# v1.net
KiCad netlist of a schematic drawn in EAGLE
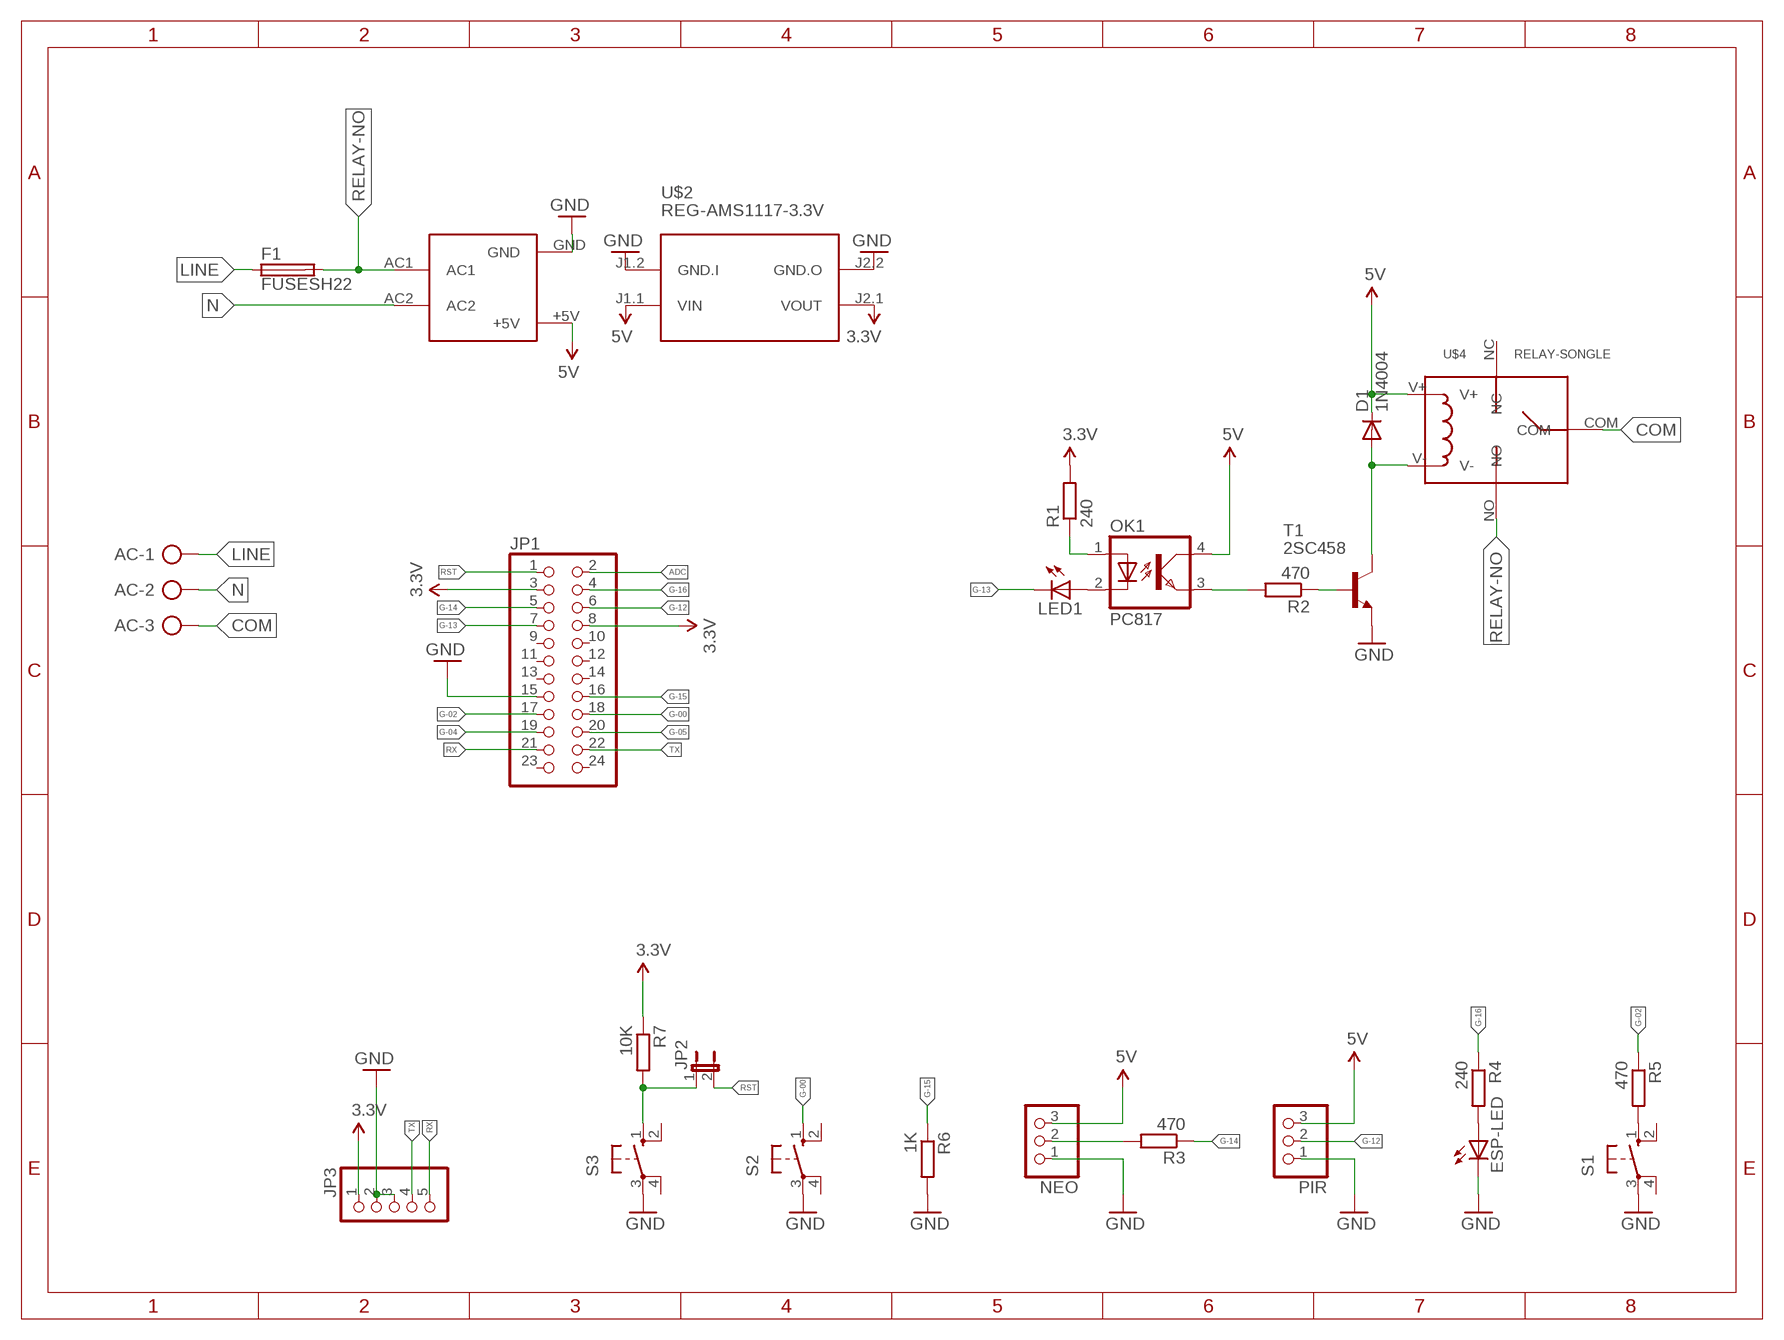
[diagram p0: schematic, sheet 1]

(export (version "E")
  (design (tool "Eeschema 10.0.6"))
  (components
    (comp (ref "AC")
      (value "AK300/3")
      (footprint "eagle-import:AK300_3")
      (libsource (lib "eagle-import") (part "AK300/3"))
    )
    (comp (ref "D1")
      (value "1N4004")
      (footprint "eagle-import:DO41-10")
      (libsource (lib "eagle-import") (part "1N4004"))
    )
    (comp (ref "ESP-LED")
      (value "LED5MM")
      (footprint "eagle-import:LED5MM")
      (libsource (lib "eagle-import") (part "LED5MM"))
    )
    (comp (ref "F1")
      (value "FUSESH22")
      (footprint "eagle-import:SH22")
      (libsource (lib "eagle-import") (part "FUSESH22"))
    )
    (comp (ref "JP1")
      (value "PINHD-2X12")
      (footprint "eagle-import:2X12")
      (libsource (lib "eagle-import") (part "PINHD-2X12"))
    )
    (comp (ref "JP2")
      (value "JUMPER-2PTH")
      (footprint "eagle-import:1X02")
      (libsource (lib "eagle-import") (part "JUMPER-2PTH"))
    )
    (comp (ref "JP3")
      (value "PINHD-1X5")
      (footprint "eagle-import:1X05")
      (libsource (lib "eagle-import") (part "PINHD-1X5"))
    )
    (comp (ref "LED1")
      (value "LED5MM")
      (footprint "eagle-import:LED5MM")
      (libsource (lib "eagle-import") (part "LED5MM"))
    )
    (comp (ref "NEO")
      (value "PINHD-1X3")
      (footprint "eagle-import:1X03")
      (libsource (lib "eagle-import") (part "PINHD-1X3"))
    )
    (comp (ref "OK1")
      (value "PC817")
      (footprint "eagle-import:DIL04")
      (fields (field (name "MPN") "PC817X4J000F"))
      (libsource (lib "eagle-import") (part "PC817"))
    )
    (comp (ref "PIR")
      (value "PINHD-1X3")
      (footprint "eagle-import:1X03")
      (libsource (lib "eagle-import") (part "PINHD-1X3"))
    )
    (comp (ref "R1")
      (value "240")
      (footprint "eagle-import:0204_5")
      (libsource (lib "eagle-import") (part "R-EU_0204/5"))
    )
    (comp (ref "R2")
      (value "470")
      (footprint "eagle-import:0204_5")
      (libsource (lib "eagle-import") (part "R-EU_0204/5"))
    )
    (comp (ref "R3")
      (value "470")
      (footprint "eagle-import:0204_5")
      (libsource (lib "eagle-import") (part "R-EU_0204/5"))
    )
    (comp (ref "R4")
      (value "240")
      (footprint "eagle-import:0204_5")
      (libsource (lib "eagle-import") (part "R-EU_0204/5"))
    )
    (comp (ref "R5")
      (value "470")
      (footprint "eagle-import:0204_5")
      (libsource (lib "eagle-import") (part "R-EU_0204/5"))
    )
    (comp (ref "R6")
      (value "1K")
      (footprint "eagle-import:0204_5")
      (libsource (lib "eagle-import") (part "R-EU_0204/5"))
    )
    (comp (ref "R7")
      (value "10K")
      (footprint "eagle-import:0204_5")
      (libsource (lib "eagle-import") (part "R-EU_0204/5"))
    )
    (comp (ref "S1")
      (value "10-XX")
      (footprint "eagle-import:B3F-10XX")
      (fields (field (name "MPN") "B3F-1000"))
      (libsource (lib "eagle-import") (part "10-XX"))
    )
    (comp (ref "S2")
      (value "10-XX")
      (footprint "eagle-import:B3F-10XX")
      (fields (field (name "MPN") "B3F-1000"))
      (libsource (lib "eagle-import") (part "10-XX"))
    )
    (comp (ref "S3")
      (value "10-XX")
      (footprint "eagle-import:B3F-10XX")
      (fields (field (name "MPN") "B3F-1000"))
      (libsource (lib "eagle-import") (part "10-XX"))
    )
    (comp (ref "T1")
      (value "2SC458")
      (footprint "eagle-import:TO92-ECB")
      (libsource (lib "eagle-import") (part "2SC458"))
    )
    (comp (ref "U$1")
      (value "HLK-PM01")
      (footprint "eagle-import:HLK-PM01")
      (libsource (lib "eagle-import") (part "HLK-PM01"))
    )
    (comp (ref "U$2")
      (value "REG-AMS1117-3.3V")
      (footprint "eagle-import:REG-AMS1117")
      (libsource (lib "eagle-import") (part "REG-AMS1117-3.3V"))
    )
    (comp (ref "U$4")
      (value "RELAY-SONGLE")
      (footprint "eagle-import:RELAY-SONGLE")
      (libsource (lib "eagle-import") (part "RELAY-SONGLE"))
    )
  )
  (nets
    (net (code "1") (name "3.3V") (class "Default")
      (node (ref "JP1") (pin "3") (pinfunction "3_3") (pintype "passive"))
      (node (ref "JP1") (pin "8") (pinfunction "8_8") (pintype "passive"))
      (node (ref "JP3") (pin "1") (pinfunction "1_1") (pintype "passive"))
      (node (ref "R1") (pin "2") (pinfunction "2_2") (pintype "passive"))
      (node (ref "R7") (pin "1") (pinfunction "1_1") (pintype "passive"))
      (node (ref "U$2") (pin "J2.1") (pinfunction "VOUT_J2.1") (pintype "bidirectional"))
    )
    (net (code "2") (name "5V") (class "Default")
      (node (ref "D1") (pin "C") (pinfunction "C_C") (pintype "passive"))
      (node (ref "NEO") (pin "3") (pinfunction "3_3") (pintype "passive"))
      (node (ref "OK1") (pin "4") (pinfunction "COL_4") (pintype "passive"))
      (node (ref "PIR") (pin "3") (pinfunction "3_3") (pintype "passive"))
      (node (ref "U$1") (pin "+5V") (pinfunction "+5V_+5V") (pintype "bidirectional"))
      (node (ref "U$2") (pin "J1.1") (pinfunction "VIN_J1.1") (pintype "bidirectional"))
      (node (ref "U$4") (pin "V+") (pinfunction "V+_V+") (pintype "bidirectional"))
    )
    (net (code "3") (name "ADC") (class "Default")
      (node (ref "JP1") (pin "2") (pinfunction "2_2") (pintype "passive"))
    )
    (net (code "4") (name "COM") (class "Default")
      (node (ref "AC") (pin "3") (pinfunction "KL_3") (pintype "passive"))
      (node (ref "U$4") (pin "COM") (pinfunction "COM_COM") (pintype "bidirectional"))
    )
    (net (code "5") (name "G-00") (class "Default")
      (node (ref "JP1") (pin "18") (pinfunction "18_18") (pintype "passive"))
      (node (ref "S2") (pin "1") (pinfunction "S_1") (pintype "passive"))
    )
    (net (code "6") (name "G-02") (class "Default")
      (node (ref "JP1") (pin "17") (pinfunction "17_17") (pintype "passive"))
      (node (ref "R5") (pin "1") (pinfunction "1_1") (pintype "passive"))
    )
    (net (code "7") (name "G-04") (class "Default")
      (node (ref "JP1") (pin "19") (pinfunction "19_19") (pintype "passive"))
    )
    (net (code "8") (name "G-05") (class "Default")
      (node (ref "JP1") (pin "20") (pinfunction "20_20") (pintype "passive"))
    )
    (net (code "9") (name "G-12") (class "Default")
      (node (ref "JP1") (pin "6") (pinfunction "6_6") (pintype "passive"))
      (node (ref "PIR") (pin "2") (pinfunction "2_2") (pintype "passive"))
    )
    (net (code "10") (name "G-13") (class "Default")
      (node (ref "JP1") (pin "7") (pinfunction "7_7") (pintype "passive"))
      (node (ref "LED1") (pin "K") (pinfunction "C_K") (pintype "passive"))
    )
    (net (code "11") (name "G-14") (class "Default")
      (node (ref "JP1") (pin "5") (pinfunction "5_5") (pintype "passive"))
      (node (ref "R3") (pin "1") (pinfunction "1_1") (pintype "passive"))
    )
    (net (code "12") (name "G-15") (class "Default")
      (node (ref "JP1") (pin "16") (pinfunction "16_16") (pintype "passive"))
      (node (ref "R6") (pin "1") (pinfunction "1_1") (pintype "passive"))
    )
    (net (code "13") (name "G-16") (class "Default")
      (node (ref "JP1") (pin "4") (pinfunction "4_4") (pintype "passive"))
      (node (ref "R4") (pin "1") (pinfunction "1_1") (pintype "passive"))
    )
    (net (code "14") (name "GND") (class "Default")
      (node (ref "ESP-LED") (pin "K") (pinfunction "C_K") (pintype "passive"))
      (node (ref "JP1") (pin "15") (pinfunction "15_15") (pintype "passive"))
      (node (ref "JP3") (pin "2") (pinfunction "2_2") (pintype "passive"))
      (node (ref "JP3") (pin "3") (pinfunction "3_3") (pintype "passive"))
      (node (ref "NEO") (pin "1") (pinfunction "1_1") (pintype "passive"))
      (node (ref "PIR") (pin "1") (pinfunction "1_1") (pintype "passive"))
      (node (ref "R6") (pin "2") (pinfunction "2_2") (pintype "passive"))
      (node (ref "S1") (pin "3") (pinfunction "P_3") (pintype "passive"))
      (node (ref "S2") (pin "3") (pinfunction "P_3") (pintype "passive"))
      (node (ref "S3") (pin "3") (pinfunction "P_3") (pintype "passive"))
      (node (ref "T1") (pin "E") (pinfunction "E_E") (pintype "passive"))
      (node (ref "U$1") (pin "GND") (pinfunction "GND_GND") (pintype "bidirectional"))
      (node (ref "U$2") (pin "J1.2") (pinfunction "GND.I_J1.2") (pintype "bidirectional"))
      (node (ref "U$2") (pin "J2.2") (pinfunction "GND.O_J2.2") (pintype "bidirectional"))
    )
    (net (code "15") (name "LINE") (class "Default")
      (node (ref "AC") (pin "1") (pinfunction "KL_1") (pintype "passive"))
      (node (ref "F1") (pin "1") (pinfunction "1_1") (pintype "passive"))
    )
    (net (code "16") (name "N") (class "Default")
      (node (ref "AC") (pin "2") (pinfunction "KL_2") (pintype "passive"))
      (node (ref "U$1") (pin "AC2") (pinfunction "AC2_AC2") (pintype "bidirectional"))
    )
    (net (code "17") (name "Net-(D1-PadA)") (class "Default")
      (node (ref "D1") (pin "A") (pinfunction "A_A") (pintype "passive"))
      (node (ref "T1") (pin "C") (pinfunction "C_C") (pintype "passive"))
      (node (ref "U$4") (pin "V-") (pinfunction "V-_V-") (pintype "bidirectional"))
    )
    (net (code "18") (name "Net-(ESP-LED-PadA)") (class "Default")
      (node (ref "ESP-LED") (pin "A") (pinfunction "A_A") (pintype "passive"))
      (node (ref "R4") (pin "2") (pinfunction "2_2") (pintype "passive"))
    )
    (net (code "19") (name "Net-(NEO-Pad2)") (class "Default")
      (node (ref "NEO") (pin "2") (pinfunction "2_2") (pintype "passive"))
      (node (ref "R3") (pin "2") (pinfunction "2_2") (pintype "passive"))
    )
    (net (code "20") (name "Net-(OK1-A)") (class "Default")
      (node (ref "OK1") (pin "1") (pinfunction "A_1") (pintype "passive"))
      (node (ref "R1") (pin "1") (pinfunction "1_1") (pintype "passive"))
    )
    (net (code "21") (name "Net-(OK1-C)") (class "Default")
      (node (ref "LED1") (pin "A") (pinfunction "A_A") (pintype "passive"))
      (node (ref "OK1") (pin "2") (pinfunction "C_2") (pintype "passive"))
    )
    (net (code "22") (name "Net-(OK1-EMIT)") (class "Default")
      (node (ref "OK1") (pin "3") (pinfunction "EMIT_3") (pintype "passive"))
      (node (ref "R2") (pin "2") (pinfunction "2_2") (pintype "passive"))
    )
    (net (code "23") (name "Net-(R2-Pad1)") (class "Default")
      (node (ref "R2") (pin "1") (pinfunction "1_1") (pintype "passive"))
      (node (ref "T1") (pin "B") (pinfunction "B_B") (pintype "passive"))
    )
    (net (code "24") (name "Net-(S1-S)") (class "Default")
      (node (ref "R5") (pin "2") (pinfunction "2_2") (pintype "passive"))
      (node (ref "S1") (pin "1") (pinfunction "S_1") (pintype "passive"))
    )
    (net (code "25") (name "Net-(S3-S)") (class "Default")
      (node (ref "JP2") (pin "1") (pinfunction "1_1") (pintype "passive"))
      (node (ref "R7") (pin "2") (pinfunction "2_2") (pintype "passive"))
      (node (ref "S3") (pin "1") (pinfunction "S_1") (pintype "passive"))
    )
    (net (code "26") (name "RELAY-NO") (class "Default")
      (node (ref "F1") (pin "2") (pinfunction "2_2") (pintype "passive"))
      (node (ref "U$1") (pin "AC1") (pinfunction "AC1_AC1") (pintype "bidirectional"))
      (node (ref "U$4") (pin "NO") (pinfunction "NO_NO") (pintype "bidirectional"))
    )
    (net (code "27") (name "RST") (class "Default")
      (node (ref "JP1") (pin "1") (pinfunction "1_1") (pintype "passive"))
      (node (ref "JP2") (pin "2") (pinfunction "2_2") (pintype "passive"))
    )
    (net (code "28") (name "RX") (class "Default")
      (node (ref "JP1") (pin "21") (pinfunction "21_21") (pintype "passive"))
      (node (ref "JP3") (pin "5") (pinfunction "5_5") (pintype "passive"))
    )
    (net (code "29") (name "TX") (class "Default")
      (node (ref "JP1") (pin "22") (pinfunction "22_22") (pintype "passive"))
      (node (ref "JP3") (pin "4") (pinfunction "4_4") (pintype "passive"))
    )
    (net (code "30") (name "unconnected-(JP1-Pad9)") (class "Default")
      (node (ref "JP1") (pin "9") (pinfunction "9_9") (pintype "passive"))
    )
    (net (code "31") (name "unconnected-(JP1-Pad10)") (class "Default")
      (node (ref "JP1") (pin "10") (pinfunction "10_10") (pintype "passive"))
    )
    (net (code "32") (name "unconnected-(JP1-Pad11)") (class "Default")
      (node (ref "JP1") (pin "11") (pinfunction "11_11") (pintype "passive"))
    )
    (net (code "33") (name "unconnected-(JP1-Pad12)") (class "Default")
      (node (ref "JP1") (pin "12") (pinfunction "12_12") (pintype "passive"))
    )
    (net (code "34") (name "unconnected-(JP1-Pad13)") (class "Default")
      (node (ref "JP1") (pin "13") (pinfunction "13_13") (pintype "passive"))
    )
    (net (code "35") (name "unconnected-(JP1-Pad14)") (class "Default")
      (node (ref "JP1") (pin "14") (pinfunction "14_14") (pintype "passive"))
    )
    (net (code "36") (name "unconnected-(JP1-Pad23)") (class "Default")
      (node (ref "JP1") (pin "23") (pinfunction "23_23") (pintype "passive"))
    )
    (net (code "37") (name "unconnected-(JP1-Pad24)") (class "Default")
      (node (ref "JP1") (pin "24") (pinfunction "24_24") (pintype "passive"))
    )
    (net (code "38") (name "unconnected-(S1-P1-Pad4)") (class "Default")
      (node (ref "S1") (pin "4") (pinfunction "P1_4") (pintype "passive"))
    )
    (net (code "39") (name "unconnected-(S1-S1-Pad2)") (class "Default")
      (node (ref "S1") (pin "2") (pinfunction "S1_2") (pintype "passive"))
    )
    (net (code "40") (name "unconnected-(S2-P1-Pad4)") (class "Default")
      (node (ref "S2") (pin "4") (pinfunction "P1_4") (pintype "passive"))
    )
    (net (code "41") (name "unconnected-(S2-S1-Pad2)") (class "Default")
      (node (ref "S2") (pin "2") (pinfunction "S1_2") (pintype "passive"))
    )
    (net (code "42") (name "unconnected-(S3-P1-Pad4)") (class "Default")
      (node (ref "S3") (pin "4") (pinfunction "P1_4") (pintype "passive"))
    )
    (net (code "43") (name "unconnected-(S3-S1-Pad2)") (class "Default")
      (node (ref "S3") (pin "2") (pinfunction "S1_2") (pintype "passive"))
    )
    (net (code "44") (name "unconnected-(U$4-PadNC)") (class "Default")
      (node (ref "U$4") (pin "NC") (pinfunction "NC_NC") (pintype "bidirectional"))
    )
  )
)
